# Schema.net
KiCad netlist of a schematic drawn in EasyEDA
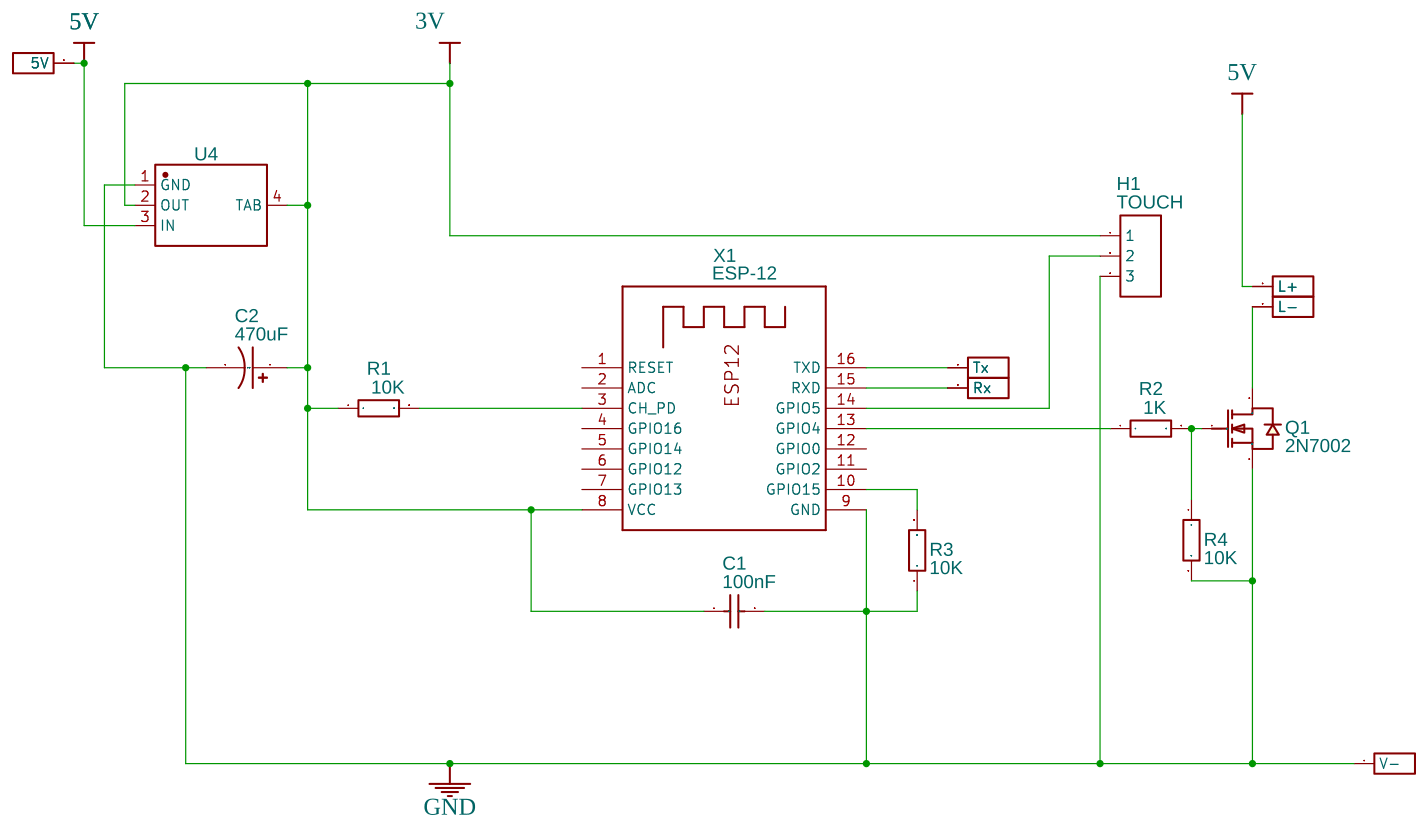
[diagram p0: schematic sheet]

(export (version "E")
  (design (tool "Eeschema 10.0.6"))
  (components
    (comp (ref "C1")
      (value "100nF")
      (fields (field (name "Manufacturer Part") "CL10B104JB8NNNC") (field (name "Manufacturer") "SAMSUNG"))
      (libsource (lib "") (part "CL10B104JB8NNNC"))
    )
    (comp (ref "C2")
      (value "470uF")
      (fields
        (field (name "Manufacturer Part") "A700V106M12RATE040")
        (field (name "Manufacturer") "KEMET(基美)")
      )
      (libsource (lib "") (part "A700V106M12RATE040"))
    )
    (comp (ref "H1") (value "TOUCH") (libsource (lib "") (part "HDR-F-2.54_1x3")))
    (comp (ref "J1") (value "HDR-M-2.54_1x1") (libsource (lib "") (part "HDR-M-2.54_1x1")))
    (comp (ref "J2") (value "HDR-M-2.54_1x1") (libsource (lib "") (part "HDR-M-2.54_1x1_4")))
    (comp (ref "J3") (value "HDR-M-2.54_1x1") (libsource (lib "") (part "HDR-M-2.54_1x1_1")))
    (comp (ref "J4") (value "HDR-M-2.54_1x1") (libsource (lib "") (part "HDR-M-2.54_1x1_3")))
    (comp (ref "J5") (value "HDR-M-2.54_1x1") (libsource (lib "") (part "HDR-M-2.54_1x1_2")))
    (comp (ref "J6") (value "HDR-M-2.54_1x1") (libsource (lib "") (part "HDR-M-2.54_1x1_5")))
    (comp (ref "Q1")
      (value "2N7002")
      (fields (field (name "Manufacturer Part") "2N7002,215") (field (name "Manufacturer") "Nexperia"))
      (libsource (lib "") (part "2N7002"))
    )
    (comp (ref "R1")
      (value "10K")
      (fields (field (name "Manufacturer Part") "RK73B1JTTD103J") (field (name "Manufacturer") "KOA"))
      (libsource (lib "") (part "RK73B1JTTD103J_1"))
    )
    (comp (ref "R2")
      (value "1K")
      (fields (field (name "Manufacturer Part") "RK73B1JTTD103J") (field (name "Manufacturer") "KOA"))
      (libsource (lib "") (part "RK73B1JTTD103J_1"))
    )
    (comp (ref "R3")
      (value "10K")
      (fields (field (name "Manufacturer Part") "RK73B1JTTD103J") (field (name "Manufacturer") "KOA"))
      (libsource (lib "") (part "RK73B1JTTD103J_2"))
    )
    (comp (ref "R4")
      (value "10K")
      (fields (field (name "Manufacturer Part") "RK73B1JTTD103J") (field (name "Manufacturer") "KOA"))
      (libsource (lib "") (part "RK73B1JTTD103J"))
    )
    (comp (ref "U4")
      (value "LT1117IST-2.85#TRPBF")
      (fields (field (name "Manufacturer") "Analog Devices"))
      (libsource (lib "") (part "LT1117IST-2.85#TRPBF"))
    )
    (comp (ref "X1") (value "ESP-12") (libsource (lib "") (part "ESP-12")))
  )
  (nets
    (net (code "1") (name "3V") (class "Default")
      (node (ref "C1") (pin "1") (pinfunction "1_1") (pintype "input"))
      (node (ref "C2") (pin "1") (pinfunction "1_1") (pintype "unspecified"))
      (node (ref "H1") (pin "1") (pinfunction "1_1") (pintype "input"))
      (node (ref "R1") (pin "1") (pinfunction "1_1") (pintype "unspecified"))
      (node (ref "U4") (pin "2") (pinfunction "OUT_2") (pintype "unspecified"))
      (node (ref "U4") (pin "4") (pinfunction "TAB_4") (pintype "unspecified"))
      (node (ref "X1") (pin "8") (pinfunction "VCC_8") (pintype "passive"))
    )
    (net (code "2") (name "5V") (class "Default")
      (node (ref "J2") (pin "1") (pinfunction "5V_1") (pintype "input"))
      (node (ref "J5") (pin "1") (pinfunction "L+_1") (pintype "input"))
      (node (ref "U4") (pin "3") (pinfunction "IN_3") (pintype "unspecified"))
    )
    (net (code "3") (name "GND") (class "Default")
      (node (ref "C1") (pin "2") (pinfunction "2_2") (pintype "input"))
      (node (ref "C2") (pin "2") (pinfunction "2_2") (pintype "unspecified"))
      (node (ref "H1") (pin "3") (pinfunction "3_3") (pintype "input"))
      (node (ref "J1") (pin "1") (pinfunction "V-_1") (pintype "input"))
      (node (ref "Q1") (pin "2") (pinfunction "S_2") (pintype "unspecified"))
      (node (ref "R3") (pin "1") (pinfunction "1_1") (pintype "unspecified"))
      (node (ref "R4") (pin "2") (pinfunction "2_2") (pintype "unspecified"))
      (node (ref "U4") (pin "1") (pinfunction "GND_1") (pintype "unspecified"))
      (node (ref "X1") (pin "9") (pinfunction "GND_9") (pintype "passive"))
    )
    (net (code "4") (name "Net-(J3-Tx)") (class "Default")
      (node (ref "J3") (pin "1") (pinfunction "Tx_1") (pintype "input"))
      (node (ref "X1") (pin "16") (pinfunction "TXD_16") (pintype "output"))
    )
    (net (code "5") (name "Net-(J4-Rx)") (class "Default")
      (node (ref "J4") (pin "1") (pinfunction "Rx_1") (pintype "input"))
      (node (ref "X1") (pin "15") (pinfunction "RXD_15") (pintype "input"))
    )
    (net (code "6") (name "Net-(J6-L-)") (class "Default")
      (node (ref "J6") (pin "1") (pinfunction "L-_1") (pintype "input"))
      (node (ref "Q1") (pin "3") (pinfunction "D_3") (pintype "unspecified"))
    )
    (net (code "7") (name "Net-(Q1-G)") (class "Default")
      (node (ref "Q1") (pin "1") (pinfunction "G_1") (pintype "unspecified"))
      (node (ref "R2") (pin "2") (pinfunction "2_2") (pintype "unspecified"))
      (node (ref "R4") (pin "1") (pinfunction "1_1") (pintype "unspecified"))
    )
    (net (code "8") (name "Net-(X1-CH_PD)") (class "Default")
      (node (ref "R1") (pin "2") (pinfunction "2_2") (pintype "unspecified"))
      (node (ref "X1") (pin "3") (pinfunction "CH_PD_3") (pintype "input"))
    )
    (net (code "9") (name "Net-(X1-GPIO4)") (class "Default")
      (node (ref "R2") (pin "1") (pinfunction "1_1") (pintype "unspecified"))
      (node (ref "X1") (pin "13") (pinfunction "GPIO4_13") (pintype "unspecified"))
    )
    (net (code "10") (name "Net-(X1-GPIO5)") (class "Default")
      (node (ref "H1") (pin "2") (pinfunction "2_2") (pintype "input"))
      (node (ref "X1") (pin "14") (pinfunction "GPIO5_14") (pintype "unspecified"))
    )
    (net (code "11") (name "Net-(X1-GPIO15)") (class "Default")
      (node (ref "R3") (pin "2") (pinfunction "2_2") (pintype "unspecified"))
      (node (ref "X1") (pin "10") (pinfunction "GPIO15_10") (pintype "unspecified"))
    )
    (net (code "12") (name "unconnected-(X1-ADC-Pad2)") (class "Default")
      (node (ref "X1") (pin "2") (pinfunction "ADC_2") (pintype "unspecified"))
    )
    (net (code "13") (name "unconnected-(X1-GPIO0-Pad12)") (class "Default")
      (node (ref "X1") (pin "12") (pinfunction "GPIO0_12") (pintype "unspecified"))
    )
    (net (code "14") (name "unconnected-(X1-GPIO2-Pad11)") (class "Default")
      (node (ref "X1") (pin "11") (pinfunction "GPIO2_11") (pintype "unspecified"))
    )
    (net (code "15") (name "unconnected-(X1-GPIO12-Pad6)") (class "Default")
      (node (ref "X1") (pin "6") (pinfunction "GPIO12_6") (pintype "unspecified"))
    )
    (net (code "16") (name "unconnected-(X1-GPIO13-Pad7)") (class "Default")
      (node (ref "X1") (pin "7") (pinfunction "GPIO13_7") (pintype "unspecified"))
    )
    (net (code "17") (name "unconnected-(X1-GPIO14-Pad5)") (class "Default")
      (node (ref "X1") (pin "5") (pinfunction "GPIO14_5") (pintype "unspecified"))
    )
    (net (code "18") (name "unconnected-(X1-GPIO16-Pad4)") (class "Default")
      (node (ref "X1") (pin "4") (pinfunction "GPIO16_4") (pintype "unspecified"))
    )
    (net (code "19") (name "unconnected-(X1-RESET-Pad1)") (class "Default")
      (node (ref "X1") (pin "1") (pinfunction "RESET_1") (pintype "input"))
    )
  )
)
